# LPS.net
KiCad netlist of a schematic drawn in Altium Designer
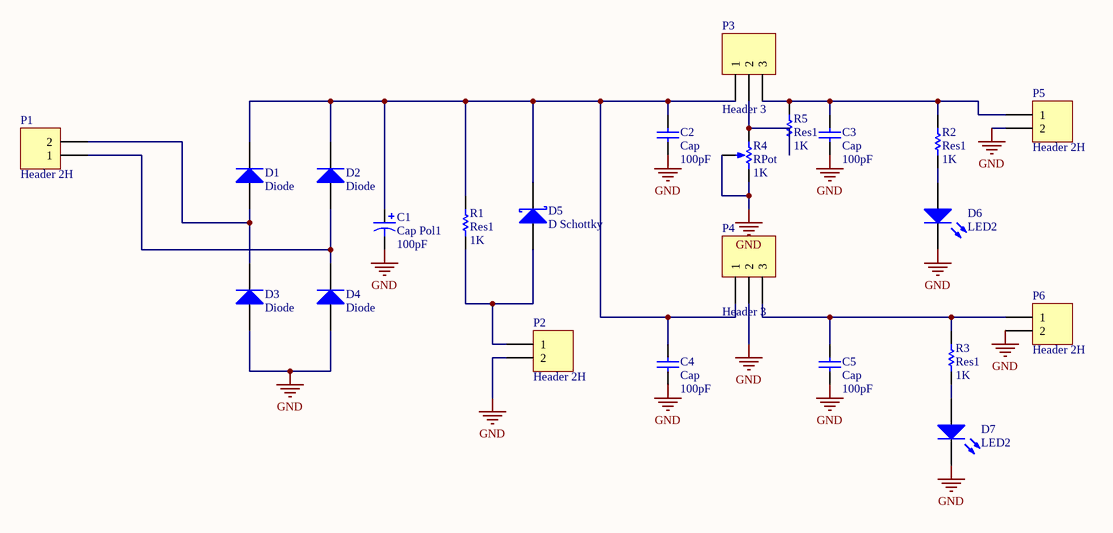
[diagram p0: LPS.SchDoc]

(export (version "E")
  (design (tool "Eeschema 10.0.6"))
  (components
    (comp (ref "C1")
      (value "Cap Pol1")
      (footprint "CAPR5-4X5")
      (description "Polarized Capacitor (Radial)")
      (fields (field (name "ALTIUM_VALUE") "100pF") (field (name "PUBLISHER") "Altium Limited"))
      (libsource (lib "Miscellaneous_Devices") (part "Cap Pol1"))
    )
    (comp (ref "C2")
      (value "Cap")
      (footprint "RAD-0.3")
      (description "Capacitor")
      (fields (field (name "ALTIUM_VALUE") "100pF") (field (name "PUBLISHER") "Altium Limited"))
      (libsource (lib "Miscellaneous_Devices") (part "Cap"))
    )
    (comp (ref "C3")
      (value "Cap")
      (footprint "RAD-0.3")
      (description "Capacitor")
      (fields (field (name "ALTIUM_VALUE") "100pF") (field (name "PUBLISHER") "Altium Limited"))
      (libsource (lib "Miscellaneous_Devices") (part "Cap"))
    )
    (comp (ref "C4")
      (value "Cap")
      (footprint "RAD-0.3")
      (description "Capacitor")
      (fields (field (name "ALTIUM_VALUE") "100pF") (field (name "PUBLISHER") "Altium Limited"))
      (libsource (lib "Miscellaneous_Devices") (part "Cap"))
    )
    (comp (ref "C5")
      (value "Cap")
      (footprint "RAD-0.3")
      (description "Capacitor")
      (fields (field (name "ALTIUM_VALUE") "100pF") (field (name "PUBLISHER") "Altium Limited"))
      (libsource (lib "Miscellaneous_Devices") (part "Cap"))
    )
    (comp (ref "D1")
      (value "Diode")
      (footprint "DIODE-0.7")
      (description "Default Diode")
      (fields (field (name "PUBLISHER") "Altium Limited"))
      (libsource (lib "Miscellaneous_Devices") (part "Diode"))
    )
    (comp (ref "D2")
      (value "Diode")
      (footprint "DIODE-0.7")
      (description "Default Diode")
      (fields (field (name "PUBLISHER") "Altium Limited"))
      (libsource (lib "Miscellaneous_Devices") (part "Diode"))
    )
    (comp (ref "D3")
      (value "Diode")
      (footprint "DIODE-0.7")
      (description "Default Diode")
      (fields (field (name "PUBLISHER") "Altium Limited"))
      (libsource (lib "Miscellaneous_Devices") (part "Diode"))
    )
    (comp (ref "D4")
      (value "Diode")
      (footprint "DIODE-0.7")
      (description "Default Diode")
      (fields (field (name "PUBLISHER") "Altium Limited"))
      (libsource (lib "Miscellaneous_Devices") (part "Diode"))
    )
    (comp (ref "D5")
      (value "D Schottky")
      (footprint "DIODE-0.7")
      (description "Schottky Diode")
      (fields (field (name "PUBLISHER") "Altium Limited"))
      (libsource (lib "Miscellaneous_Devices") (part "D Schottky"))
    )
    (comp (ref "D6")
      (value "LED2")
      (footprint "DIODE-0.7")
      (description "Typical RED, GREEN, YELLOW, AMBER GaAs LED")
      (fields (field (name "PUBLISHER") "Altium Limited"))
      (libsource (lib "Miscellaneous_Devices") (part "LED2"))
    )
    (comp (ref "D7")
      (value "LED2")
      (footprint "DIODE-0.7")
      (description "Typical RED, GREEN, YELLOW, AMBER GaAs LED")
      (fields (field (name "PUBLISHER") "Altium Limited"))
      (libsource (lib "Miscellaneous_Devices") (part "LED2"))
    )
    (comp (ref "P1")
      (value "Header 2H")
      (footprint "HDR1X2H")
      (description "Header, 2-Pin, Right Angle")
      (fields (field (name "PUBLISHER") "Altium Limited"))
      (libsource (lib "") (part "Header 2H_1"))
    )
    (comp (ref "P2")
      (value "Header 2H")
      (footprint "HDR1X2H")
      (description "Header, 2-Pin, Right Angle")
      (fields (field (name "PUBLISHER") "Altium Limited"))
      (libsource (lib "Miscellaneous_Connectors") (part "Header 2H"))
    )
    (comp (ref "P3")
      (value "Header 3")
      (footprint "HDR1X3")
      (description "Header, 3-Pin")
      (fields (field (name "PUBLISHER") "Altium Limited"))
      (libsource (lib "Miscellaneous_Connectors") (part "Header 3"))
    )
    (comp (ref "P4")
      (value "Header 3")
      (footprint "HDR1X3")
      (description "Header, 3-Pin")
      (fields (field (name "PUBLISHER") "Altium Limited"))
      (libsource (lib "Miscellaneous_Connectors") (part "Header 3"))
    )
    (comp (ref "P5")
      (value "Header 2H")
      (footprint "HDR1X2H")
      (description "Header, 2-Pin, Right Angle")
      (fields (field (name "PUBLISHER") "Altium Limited"))
      (libsource (lib "Miscellaneous_Connectors") (part "Header 2H"))
    )
    (comp (ref "P6")
      (value "Header 2H")
      (footprint "HDR1X2H")
      (description "Header, 2-Pin, Right Angle")
      (fields (field (name "PUBLISHER") "Altium Limited"))
      (libsource (lib "Miscellaneous_Connectors") (part "Header 2H"))
    )
    (comp (ref "R1")
      (value "Res1")
      (footprint "AXIAL-0.3")
      (description "Resistor")
      (fields (field (name "ALTIUM_VALUE") "1K") (field (name "PUBLISHER") "Altium Limited"))
      (libsource (lib "Miscellaneous_Devices") (part "Res1"))
    )
    (comp (ref "R2")
      (value "Res1")
      (footprint "AXIAL-0.3")
      (description "Resistor")
      (fields (field (name "ALTIUM_VALUE") "1K") (field (name "PUBLISHER") "Altium Limited"))
      (libsource (lib "Miscellaneous_Devices") (part "Res1"))
    )
    (comp (ref "R3")
      (value "Res1")
      (footprint "AXIAL-0.3")
      (description "Resistor")
      (fields (field (name "ALTIUM_VALUE") "1K") (field (name "PUBLISHER") "Altium Limited"))
      (libsource (lib "Miscellaneous_Devices") (part "Res1"))
    )
    (comp (ref "R4")
      (value "RPot")
      (footprint "VR5")
      (description "Potentiometer")
      (fields (field (name "ALTIUM_VALUE") "1K") (field (name "PUBLISHER") "Altium Limited"))
      (libsource (lib "Miscellaneous_Devices") (part "RPot"))
    )
    (comp (ref "R5")
      (value "Res1")
      (footprint "AXIAL-0.3")
      (description "Resistor")
      (fields (field (name "ALTIUM_VALUE") "1K") (field (name "PUBLISHER") "Altium Limited"))
      (libsource (lib "Miscellaneous_Devices") (part "Res1"))
    )
  )
  (nets
    (net (code "1") (name "GND") (class "Default")
      (node (ref "C1") (pin "2") (pinfunction "2_2") (pintype "passive"))
      (node (ref "C2") (pin "1") (pinfunction "1_1") (pintype "passive"))
      (node (ref "C3") (pin "1") (pinfunction "1_1") (pintype "passive"))
      (node (ref "C4") (pin "1") (pinfunction "1_1") (pintype "passive"))
      (node (ref "C5") (pin "1") (pinfunction "1_1") (pintype "passive"))
      (node (ref "D3") (pin "1") (pinfunction "A_1") (pintype "passive"))
      (node (ref "D4") (pin "1") (pinfunction "A_1") (pintype "passive"))
      (node (ref "D6") (pin "2") (pinfunction "K_2") (pintype "passive"))
      (node (ref "D7") (pin "2") (pinfunction "K_2") (pintype "passive"))
      (node (ref "P2") (pin "2") (pinfunction "2_2") (pintype "passive"))
      (node (ref "P4") (pin "2") (pinfunction "2_2") (pintype "passive"))
      (node (ref "P5") (pin "2") (pinfunction "2_2") (pintype "passive"))
      (node (ref "P6") (pin "2") (pinfunction "2_2") (pintype "passive"))
      (node (ref "R4") (pin "2") (pinfunction "BOT_2") (pintype "passive"))
      (node (ref "R4") (pin "3") (pinfunction "TAP_3") (pintype "passive"))
    )
    (net (code "2") (name "Net-(C3-Pad2)") (class "Default")
      (node (ref "C3") (pin "2") (pinfunction "2_2") (pintype "passive"))
      (node (ref "P3") (pin "3") (pinfunction "3_3") (pintype "passive"))
      (node (ref "P5") (pin "1") (pinfunction "1_1") (pintype "passive"))
      (node (ref "R2") (pin "2") (pinfunction "2_2") (pintype "passive"))
      (node (ref "R5") (pin "2") (pinfunction "2_2") (pintype "passive"))
    )
    (net (code "3") (name "Net-(C5-Pad2)") (class "Default")
      (node (ref "C5") (pin "2") (pinfunction "2_2") (pintype "passive"))
      (node (ref "P4") (pin "3") (pinfunction "3_3") (pintype "passive"))
      (node (ref "P6") (pin "1") (pinfunction "1_1") (pintype "passive"))
      (node (ref "R3") (pin "2") (pinfunction "2_2") (pintype "passive"))
    )
    (net (code "4") (name "Net-(D1-A)") (class "Default")
      (node (ref "D1") (pin "1") (pinfunction "A_1") (pintype "passive"))
      (node (ref "D3") (pin "2") (pinfunction "K_2") (pintype "passive"))
      (node (ref "P1") (pin "2") (pinfunction "2_2") (pintype "passive"))
    )
    (net (code "5") (name "Net-(D1-K)") (class "Default")
      (node (ref "C1") (pin "1") (pinfunction "1_1") (pintype "passive"))
      (node (ref "C2") (pin "2") (pinfunction "2_2") (pintype "passive"))
      (node (ref "C4") (pin "2") (pinfunction "2_2") (pintype "passive"))
      (node (ref "D1") (pin "2") (pinfunction "K_2") (pintype "passive"))
      (node (ref "D2") (pin "2") (pinfunction "K_2") (pintype "passive"))
      (node (ref "D5") (pin "2") (pinfunction "K_2") (pintype "passive"))
      (node (ref "P3") (pin "1") (pinfunction "1_1") (pintype "passive"))
      (node (ref "P4") (pin "1") (pinfunction "1_1") (pintype "passive"))
      (node (ref "R1") (pin "2") (pinfunction "2_2") (pintype "passive"))
    )
    (net (code "6") (name "Net-(D2-A)") (class "Default")
      (node (ref "D2") (pin "1") (pinfunction "A_1") (pintype "passive"))
      (node (ref "D4") (pin "2") (pinfunction "K_2") (pintype "passive"))
      (node (ref "P1") (pin "1") (pinfunction "1_1") (pintype "passive"))
    )
    (net (code "7") (name "Net-(D5-A)") (class "Default")
      (node (ref "D5") (pin "1") (pinfunction "A_1") (pintype "passive"))
      (node (ref "P2") (pin "1") (pinfunction "1_1") (pintype "passive"))
      (node (ref "R1") (pin "1") (pinfunction "1_1") (pintype "passive"))
    )
    (net (code "8") (name "Net-(D6-A)") (class "Default")
      (node (ref "D6") (pin "1") (pinfunction "A_1") (pintype "passive"))
      (node (ref "R2") (pin "1") (pinfunction "1_1") (pintype "passive"))
    )
    (net (code "9") (name "Net-(D7-A)") (class "Default")
      (node (ref "D7") (pin "1") (pinfunction "A_1") (pintype "passive"))
      (node (ref "R3") (pin "1") (pinfunction "1_1") (pintype "passive"))
    )
    (net (code "10") (name "Net-(R4-TOP)") (class "Default")
      (node (ref "P3") (pin "2") (pinfunction "2_2") (pintype "passive"))
      (node (ref "R4") (pin "1") (pinfunction "TOP_1") (pintype "passive"))
      (node (ref "R5") (pin "1") (pinfunction "1_1") (pintype "passive"))
    )
  )
)
